# Urukul_FPGA_Config.net
KiCad netlist of a schematic drawn in Altium Designer
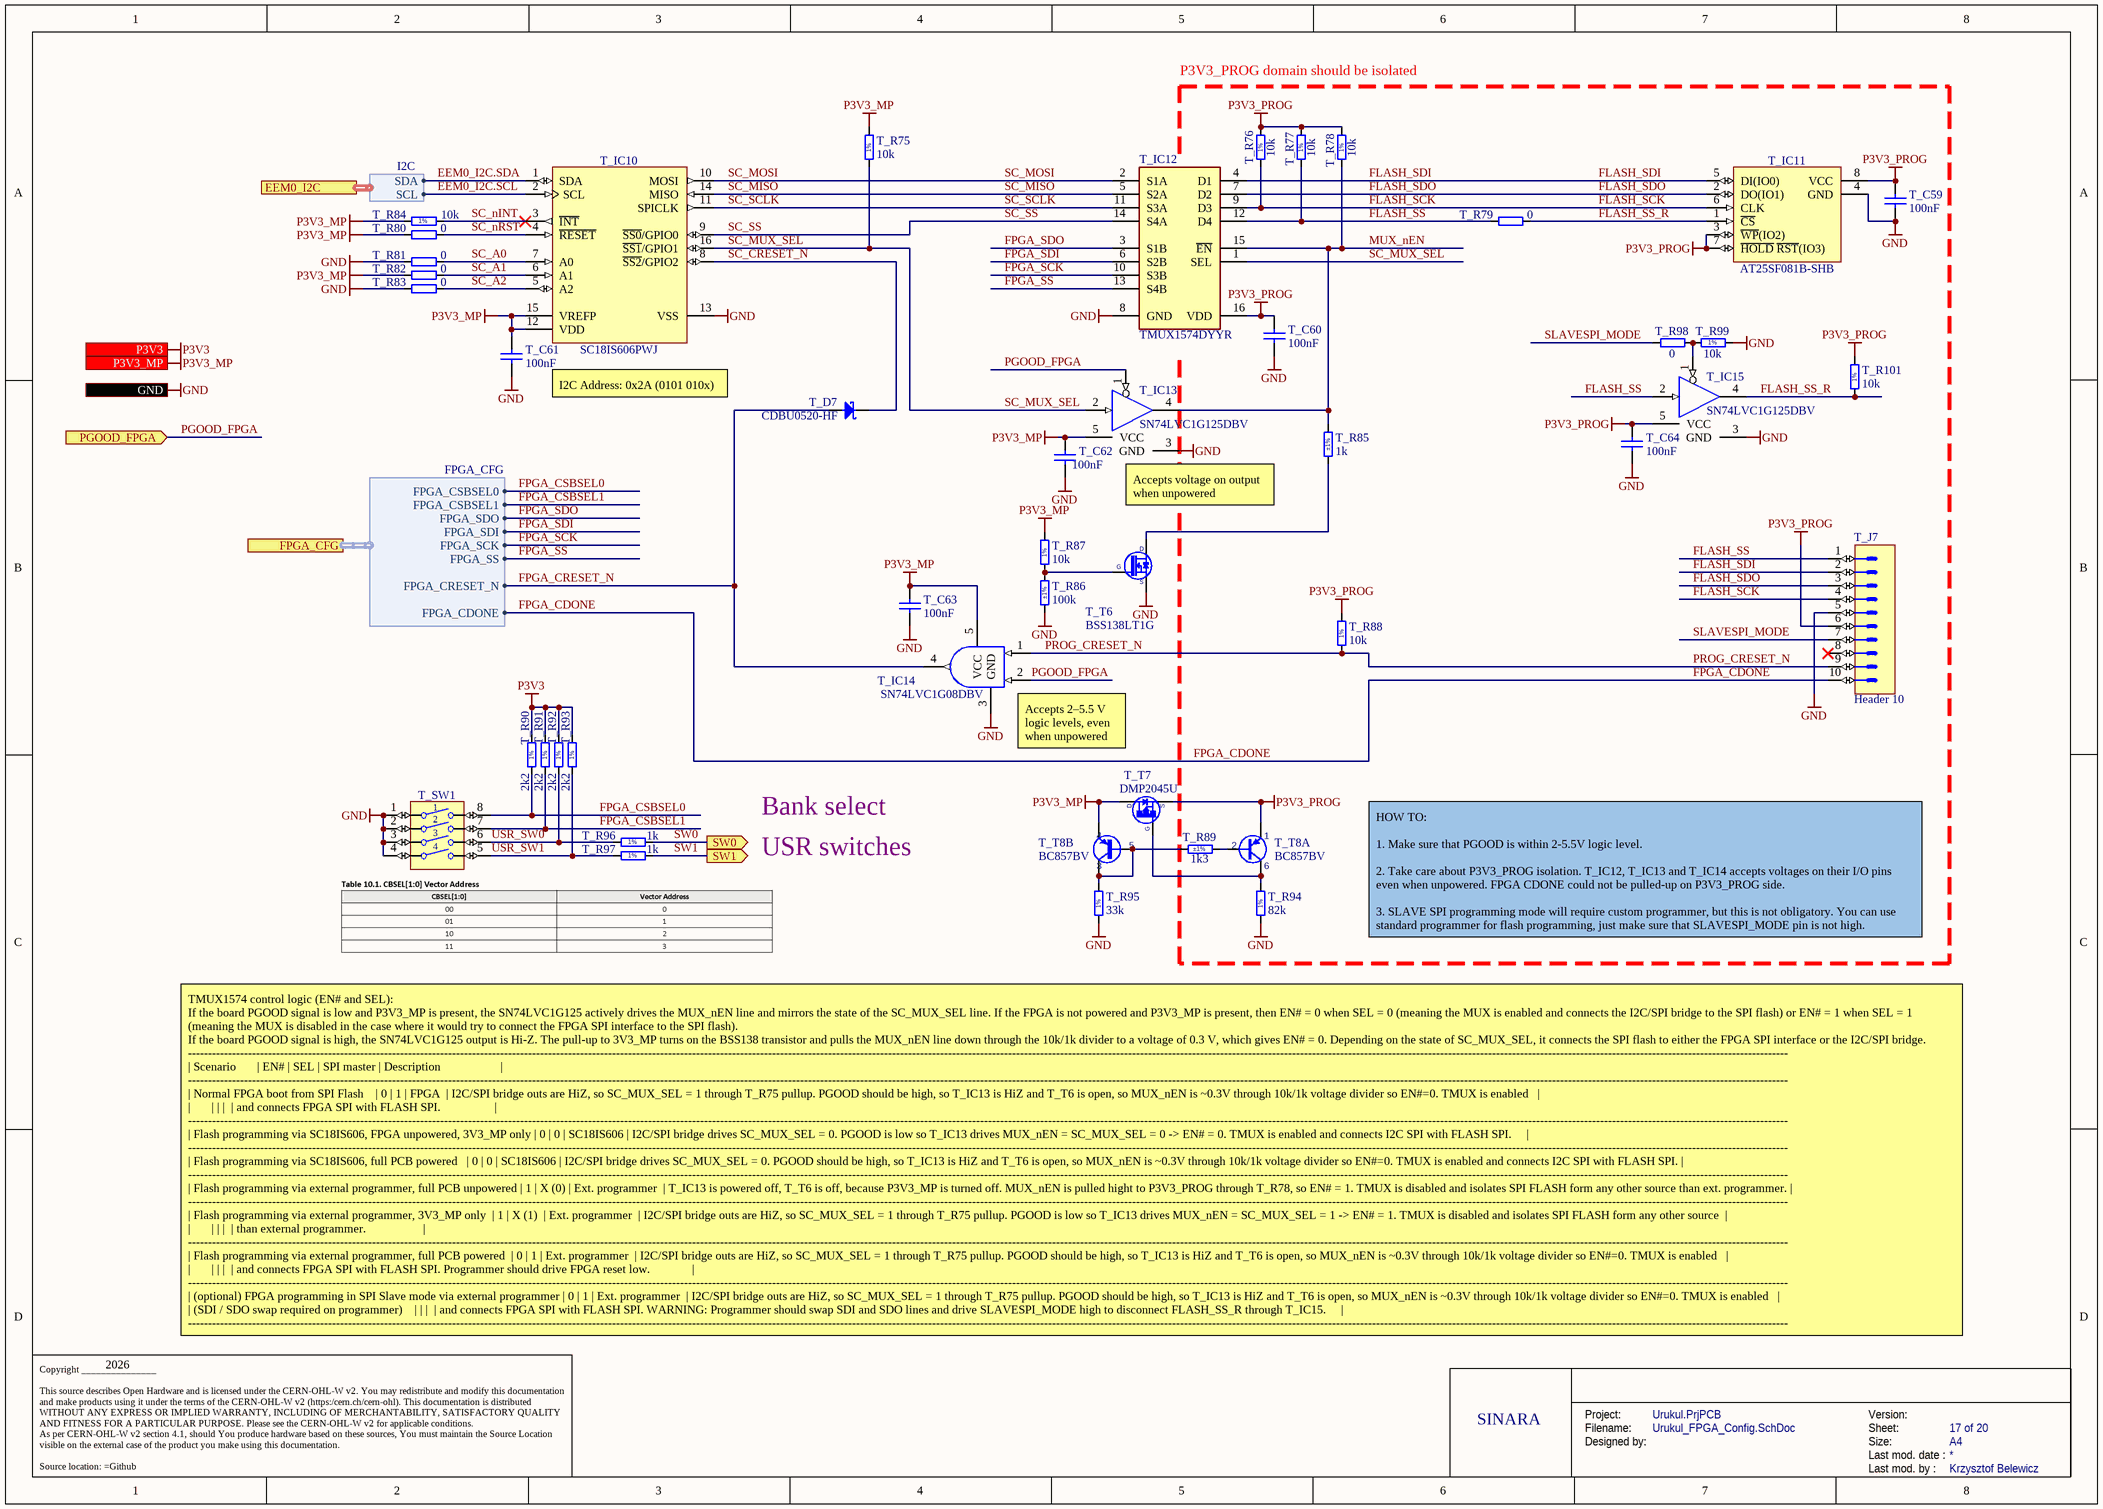
[diagram p0: Urukul_FPGA_Config.SchDoc]

(export (version "E")
  (design (tool "Eeschema 10.0.6"))
  (components
    (comp (ref "T_C59")
      (value "100nF")
      (footprint "CAPC1005X55N")
      (description "Non-polarised capacitor")
      (fields
        (field (name "PART NUMBER") "CC0402_100NF_16V_10%_X5R")
        (field (name "VOLTAGE") "16V")
        (field (name "AUTHOR") "CERN DEM JLC")
      )
      (libsource (lib "Capacitors") (part "Capacitor - non polarized"))
    )
    (comp (ref "T_C60")
      (value "100nF")
      (footprint "CAPC1005X55N")
      (description "Non-polarised capacitor")
      (fields
        (field (name "PART NUMBER") "CC0402_100NF_16V_10%_X5R")
        (field (name "VOLTAGE") "16V")
        (field (name "AUTHOR") "CERN DEM JLC")
      )
      (libsource (lib "Capacitors") (part "Capacitor - non polarized"))
    )
    (comp (ref "T_C61")
      (value "100nF")
      (footprint "CAPC1005X55N")
      (description "Non-polarised capacitor")
      (fields
        (field (name "PART NUMBER") "CC0402_100NF_16V_10%_X5R")
        (field (name "VOLTAGE") "16V")
        (field (name "AUTHOR") "CERN DEM JLC")
      )
      (libsource (lib "Capacitors") (part "Capacitor - non polarized"))
    )
    (comp (ref "T_C62")
      (value "100nF")
      (footprint "CAPC1005X55N")
      (description "Non-polarised capacitor")
      (fields
        (field (name "PART NUMBER") "CC0402_100NF_16V_10%_X5R")
        (field (name "VOLTAGE") "16V")
        (field (name "AUTHOR") "CERN DEM JLC")
      )
      (libsource (lib "Capacitors") (part "Capacitor - non polarized"))
    )
    (comp (ref "T_C63")
      (value "100nF")
      (footprint "CAPC1005X55N")
      (description "Non-polarised capacitor")
      (fields
        (field (name "PART NUMBER") "CC0402_100NF_16V_10%_X5R")
        (field (name "VOLTAGE") "16V")
        (field (name "AUTHOR") "CERN DEM JLC")
      )
      (libsource (lib "Capacitors") (part "Capacitor - non polarized"))
    )
    (comp (ref "T_C64")
      (value "100nF")
      (footprint "CAPC1005X55N")
      (description "Non-polarised capacitor")
      (fields
        (field (name "PART NUMBER") "CC0402_100NF_16V_10%_X5R")
        (field (name "VOLTAGE") "16V")
        (field (name "AUTHOR") "CERN DEM JLC")
      )
      (libsource (lib "Capacitors") (part "Capacitor - non polarized"))
    )
    (comp (ref "T_D7")
      (value "CDBU0520-HF")
      (footprint "SOD-523F")
      (description "Schottky Diode")
      (fields
        (field (name "VOLTAGE") "20V")
        (field (name "POWER") "500mA")
        (field (name "AUTHOR") "CERN DEM HF")
      )
      (libsource (lib "ICs And Semiconductors") (part "Diode Schottky"))
    )
    (comp (ref "T_IC10")
      (value "SC18IS606PWJ")
      (footprint "SOP65P640X110-16N")
      (description "I2C-bus to SPI bridge")
      (fields (field (name "MANUFACTURER") "NXP SEMICONDUCTORS") (field (name "AUTHOR") "GK"))
      (libsource (lib "ICS-logic") (part "SC18IS606PWJ"))
    )
    (comp (ref "T_IC11")
      (value "AT25SF081B-SHB")
      (footprint "SOIC127P790X216-8N")
      (description "8M-bit Serial Flash Memory with uniform 4KB sectors and Dual/Quad SPI and QPI")
      (fields (field (name "MANUFACTURER") "Renesas") (field (name "AUTHOR") "GK"))
      (libsource (lib "ICS-logic") (part "MEM_AT25SF081B-SHB"))
    )
    (comp (ref "T_IC12")
      (value "TMUX1574DYYR")
      (footprint "SamacSys:SOP50P326X110-16N")
      (description "Integrated Circuit")
      (fields (field (name "MOUSER PART NUMBER") "595-TMUX1574DYYR"))
      (libsource (lib "SamacSys") (part "TMUX1574DYYR"))
    )
    (comp (ref "T_IC13")
      (value "SN74LVC1G125DBV")
      (footprint "SOT95P280X145-5N")
      (description "Single Bus Buffer Gate With 3-State Output")
      (fields (field (name "MANUFACTURER") "TEXAS INSTRUMENTS") (field (name "AUTHOR") "CERN DEM HF"))
      (libsource (lib "ICs And Semiconductors") (part "741G125"))
    )
    (comp (ref "T_IC14")
      (value "SN74LVC1G08DBV")
      (footprint "SOT95P280X145-5N")
      (description "Single 2-Input AND Gate")
      (fields (field (name "MANUFACTURER") "TEXAS INSTRUMENTS") (field (name "AUTHOR") "CERN DEM JLC"))
      (libsource (lib "ICs And Semiconductors") (part "741G08"))
    )
    (comp (ref "T_IC15")
      (value "SN74LVC1G125DBV")
      (footprint "SOT95P280X145-5N")
      (description "Single Bus Buffer Gate With 3-State Output")
      (fields (field (name "MANUFACTURER") "TEXAS INSTRUMENTS") (field (name "AUTHOR") "CERN DEM HF"))
      (libsource (lib "ICs And Semiconductors") (part "741G125"))
    )
    (comp (ref "T_J7")
      (value "Header 10")
      (footprint "HARWIN_M20-9980546")
      (description "Connector 10 Male")
      (fields
        (field (name "PART NUMBER") "HARWIN_M20-9980546")
        (field (name "MANUFACTURER") "HARWIN")
        (field (name "AUTHOR") "CERN DEM MR")
      )
      (libsource (lib "Connectors") (part "Connector 10 Male"))
    )
    (comp (ref "T_R75")
      (value "10k")
      (footprint "RESC1005X40N")
      (description "Resistor - 1%")
      (fields
        (field (name "PART NUMBER") "R0402_10K_1%_0.0625W_100PPM")
        (field (name "POWER") "0.0625W")
        (field (name "AUTHOR") "CERN DEM JLC")
      )
      (libsource (lib "Resistors") (part "Resistor - 1%"))
    )
    (comp (ref "T_R76")
      (value "10k")
      (footprint "RESC1005X40N")
      (description "Resistor - 1%")
      (fields
        (field (name "PART NUMBER") "R0402_10K_1%_0.0625W_100PPM")
        (field (name "POWER") "0.0625W")
        (field (name "AUTHOR") "CERN DEM JLC")
      )
      (libsource (lib "Resistors") (part "Resistor - 1%"))
    )
    (comp (ref "T_R77")
      (value "10k")
      (footprint "RESC1005X40N")
      (description "Resistor - 1%")
      (fields
        (field (name "PART NUMBER") "R0402_10K_1%_0.0625W_100PPM")
        (field (name "POWER") "0.0625W")
        (field (name "AUTHOR") "CERN DEM JLC")
      )
      (libsource (lib "Resistors") (part "Resistor - 1%"))
    )
    (comp (ref "T_R78")
      (value "10k")
      (footprint "RESC1005X40N")
      (description "Resistor - 1%")
      (fields
        (field (name "PART NUMBER") "R0402_10K_1%_0.0625W_100PPM")
        (field (name "POWER") "0.0625W")
        (field (name "AUTHOR") "CERN DEM JLC")
      )
      (libsource (lib "Resistors") (part "Resistor - 1%"))
    )
    (comp (ref "T_R79")
      (value "0")
      (footprint "RESC1005X40N")
      (description "Resistor")
      (fields
        (field (name "PART NUMBER") "R0402_0R_JUMPER")
        (field (name "MANUFACTURER") "GENERIC")
        (field (name "AUTHOR") "CERN DEM JLC")
      )
      (libsource (lib "Resistors") (part "Resistor"))
    )
    (comp (ref "T_R80")
      (value "0")
      (footprint "RESC1005X40N")
      (description "Resistor")
      (fields
        (field (name "PART NUMBER") "R0402_0R_JUMPER")
        (field (name "MANUFACTURER") "GENERIC")
        (field (name "AUTHOR") "CERN DEM JLC")
      )
      (libsource (lib "Resistors") (part "Resistor"))
    )
    (comp (ref "T_R81")
      (value "0")
      (footprint "RESC1005X40N")
      (description "Resistor")
      (fields
        (field (name "PART NUMBER") "R0402_0R_JUMPER")
        (field (name "MANUFACTURER") "GENERIC")
        (field (name "AUTHOR") "CERN DEM JLC")
      )
      (libsource (lib "Resistors") (part "Resistor"))
    )
    (comp (ref "T_R82")
      (value "0")
      (footprint "RESC1005X40N")
      (description "Resistor")
      (fields
        (field (name "PART NUMBER") "R0402_0R_JUMPER")
        (field (name "MANUFACTURER") "GENERIC")
        (field (name "AUTHOR") "CERN DEM JLC")
      )
      (libsource (lib "Resistors") (part "Resistor"))
    )
    (comp (ref "T_R83")
      (value "0")
      (footprint "RESC1005X40N")
      (description "Resistor")
      (fields
        (field (name "PART NUMBER") "R0402_0R_JUMPER")
        (field (name "MANUFACTURER") "GENERIC")
        (field (name "AUTHOR") "CERN DEM JLC")
      )
      (libsource (lib "Resistors") (part "Resistor"))
    )
    (comp (ref "T_R84")
      (value "10k")
      (footprint "RESC1005X40N")
      (description "Resistor - 1%")
      (fields
        (field (name "PART NUMBER") "R0402_10K_1%_0.0625W_100PPM")
        (field (name "POWER") "0.0625W")
        (field (name "AUTHOR") "CERN DEM JLC")
      )
      (libsource (lib "Resistors") (part "Resistor - 1%"))
    )
    (comp (ref "T_R85")
      (value "1k")
      (footprint "RESC1005X40N")
      (description "Resistor - 1%")
      (fields
        (field (name "TOLERANCE") "±1%")
        (field (name "PART NUMBER") "R0402_1K_1%_0.0625W_100PPM")
        (field (name "POWER") "0.0625W")
        (field (name "AUTHOR") "CERN DEM JLC")
      )
      (libsource (lib "Resistors") (part "Resistor - 1%"))
    )
    (comp (ref "T_R86")
      (value "100k")
      (footprint "RESC1005X40N")
      (description "Resistor - 1%")
      (fields
        (field (name "TOLERANCE") "±1%")
        (field (name "PART NUMBER") "R0402_100K_1%_0.0625W_100PPM")
        (field (name "POWER") "0.0625W")
        (field (name "AUTHOR") "CERN DEM JLC")
      )
      (libsource (lib "Resistors") (part "Resistor - 1%"))
    )
    (comp (ref "T_R87")
      (value "10k")
      (footprint "RESC1005X40N")
      (description "Resistor - 1%")
      (fields
        (field (name "PART NUMBER") "R0402_10K_1%_0.0625W_100PPM")
        (field (name "POWER") "0.0625W")
        (field (name "AUTHOR") "CERN DEM JLC")
      )
      (libsource (lib "Resistors") (part "Resistor - 1%"))
    )
    (comp (ref "T_R88")
      (value "10k")
      (footprint "RESC1005X40N")
      (description "Resistor - 1%")
      (fields
        (field (name "PART NUMBER") "R0402_10K_1%_0.0625W_100PPM")
        (field (name "POWER") "0.0625W")
        (field (name "AUTHOR") "CERN DEM JLC")
      )
      (libsource (lib "Resistors") (part "Resistor - 1%"))
    )
    (comp (ref "T_R89")
      (value "1k3")
      (footprint "RESC1005X40N")
      (description "Resistor - 1%")
      (fields
        (field (name "TOLERANCE") "±1%")
        (field (name "PART NUMBER") "R0402_1K3_1%_0.0625W_100PPM")
        (field (name "POWER") "0.0625W")
        (field (name "AUTHOR") "CERN DEM JLC")
      )
      (libsource (lib "Resistors") (part "Resistor - 1%"))
    )
    (comp (ref "T_R90")
      (value "2k2")
      (footprint "RESC1005X40N")
      (description "Resistor - 1%")
      (fields
        (field (name "PART NUMBER") "R0402_2K2_1%_0.0625W_100PPM")
        (field (name "POWER") "0.0625W")
        (field (name "AUTHOR") "CERN DEM JLC")
      )
      (libsource (lib "Resistors") (part "Resistor - 1%"))
    )
    (comp (ref "T_R91")
      (value "2k2")
      (footprint "RESC1005X40N")
      (description "Resistor - 1%")
      (fields
        (field (name "PART NUMBER") "R0402_2K2_1%_0.0625W_100PPM")
        (field (name "POWER") "0.0625W")
        (field (name "AUTHOR") "CERN DEM JLC")
      )
      (libsource (lib "Resistors") (part "Resistor - 1%"))
    )
    (comp (ref "T_R92")
      (value "2k2")
      (footprint "RESC1005X40N")
      (description "Resistor - 1%")
      (fields
        (field (name "PART NUMBER") "R0402_2K2_1%_0.0625W_100PPM")
        (field (name "POWER") "0.0625W")
        (field (name "AUTHOR") "CERN DEM JLC")
      )
      (libsource (lib "Resistors") (part "Resistor - 1%"))
    )
    (comp (ref "T_R93")
      (value "2k2")
      (footprint "RESC1005X40N")
      (description "Resistor - 1%")
      (fields
        (field (name "PART NUMBER") "R0402_2K2_1%_0.0625W_100PPM")
        (field (name "POWER") "0.0625W")
        (field (name "AUTHOR") "CERN DEM JLC")
      )
      (libsource (lib "Resistors") (part "Resistor - 1%"))
    )
    (comp (ref "T_R94")
      (value "82k")
      (footprint "RESC1608X55N")
      (description "Resistor - 1%")
      (fields
        (field (name "PART NUMBER") "R0603_82K_1%_0.1W_100PPM")
        (field (name "POWER") "0.1W")
        (field (name "AUTHOR") "CERN DEM JLC")
      )
      (libsource (lib "Resistors") (part "Resistor - 1%"))
    )
    (comp (ref "T_R95")
      (value "33k")
      (footprint "RESC1005X40N")
      (description "Resistor - 1%")
      (fields
        (field (name "PART NUMBER") "R0402_33K_1%_0.0625W_100PPM")
        (field (name "POWER") "0.0625W")
        (field (name "AUTHOR") "CERN DEM JLC")
      )
      (libsource (lib "Resistors") (part "Resistor - 1%"))
    )
    (comp (ref "T_R96")
      (value "1k")
      (footprint "RESC1005X40N")
      (description "Resistor - 1%")
      (fields
        (field (name "PART NUMBER") "R0402_1K_1%_0.0625W_100PPM")
        (field (name "POWER") "0.0625W")
        (field (name "AUTHOR") "CERN DEM JLC")
      )
      (libsource (lib "Resistors") (part "Resistor - 1%"))
    )
    (comp (ref "T_R97")
      (value "1k")
      (footprint "RESC1005X40N")
      (description "Resistor - 1%")
      (fields
        (field (name "PART NUMBER") "R0402_1K_1%_0.0625W_100PPM")
        (field (name "POWER") "0.0625W")
        (field (name "AUTHOR") "CERN DEM JLC")
      )
      (libsource (lib "Resistors") (part "Resistor - 1%"))
    )
    (comp (ref "T_R98")
      (value "0")
      (footprint "RESC1005X40N")
      (description "Resistor")
      (fields
        (field (name "PART NUMBER") "R0402_0R_JUMPER")
        (field (name "MANUFACTURER") "GENERIC")
        (field (name "AUTHOR") "CERN DEM JLC")
      )
      (libsource (lib "Resistors") (part "Resistor"))
    )
    (comp (ref "T_R99")
      (value "10k")
      (footprint "RESC1005X40N")
      (description "Resistor - 1%")
      (fields
        (field (name "PART NUMBER") "R0402_10K_1%_0.0625W_100PPM")
        (field (name "POWER") "0.0625W")
        (field (name "AUTHOR") "CERN DEM JLC")
      )
      (libsource (lib "Resistors") (part "Resistor - 1%"))
    )
    (comp (ref "T_R101")
      (value "10k")
      (footprint "RESC1005X40N")
      (description "Resistor - 1%")
      (fields
        (field (name "PART NUMBER") "R0402_10K_1%_0.0625W_100PPM")
        (field (name "POWER") "0.0625W")
        (field (name "AUTHOR") "CERN DEM JLC")
      )
      (libsource (lib "Resistors") (part "Resistor - 1%"))
    )
    (comp (ref "T_SW1")
      (value "Switch")
      (footprint "SW_TYCO_1571983-4")
      (description "4 Ways SPST DIP Switch")
      (fields
        (field (name "PART NUMBER") "SW_TYCO_1571983-4")
        (field (name "MANUFACTURER") "TYCO")
        (field (name "AUTHOR") "CERN DEM JLC")
      )
      (libsource (lib "Eletro-mechanical") (part "SW 4x SPST DIP Switch"))
    )
    (comp (ref "T_T6")
      (value "BSS138LT1G")
      (footprint "SOT95P240X110-3N")
      (description "N-CHANNEL MOSFET WITH DIODE")
      (fields
        (field (name "MANUFACTURER") "ON SEMICONDUCTOR")
        (field (name "MANUFACTURER PART NUMBER") "BSS138L")
        (field (name "AUTHOR") "CERN DEM JLC")
      )
      (libsource (lib "ICs And Semiconductors") (part "N-MOSFET-D 1G 2S 3D"))
    )
    (comp (ref "T_T7")
      (value "DMP2045U")
      (footprint "SOT95P240X110-3N")
      (description "P-CHANNEL MOSFET WITH DIODE")
      (fields (field (name "MANUFACTURER") "DIODES INCORPORATED") (field (name "AUTHOR") "CERN DEM HF"))
      (libsource (lib "ICs And Semiconductors") (part "P-MOSFET-D 1G 2S 3D"))
    )
    (comp (ref "T_T8")
      (value "BC857BV")
      (footprint "SOTFL50P160X60-6N")
      (description "45V, 100mA PNP General Purpose Double Transistor")
      (fields (field (name "MANUFACTURER") "NXP SEMICONDUCTORS") (field (name "AUTHOR") "CERN DEM JLC"))
      (libsource (lib "") (part "BC857BV_1"))
    )
  )
  (nets
    (net (code "3") (name "/EEM0_I2C.SCL") (class "Default")
      (node (ref "T_IC10") (pin "2") (pinfunction "SCL_2") (pintype "input"))
    )
    (net (code "4") (name "/EEM0_I2C.SDA") (class "Default")
      (node (ref "T_IC10") (pin "1") (pinfunction "SDA_1") (pintype "bidirectional"))
    )
    (net (code "5") (name "/FLASH_SCK") (class "Default")
      (node (ref "T_IC11") (pin "6") (pinfunction "CLK_6") (pintype "input"))
      (node (ref "T_IC12") (pin "9") (pinfunction "D3_9") (pintype "passive"))
      (node (ref "T_J7") (pin "4") (pinfunction "4_4") (pintype "bidirectional"))
      (node (ref "T_R76") (pin "1") (pinfunction "1_1") (pintype "passive"))
    )
    (net (code "6") (name "/FLASH_SDI") (class "Default")
      (node (ref "T_IC11") (pin "5") (pinfunction "DI(IO0)_5") (pintype "bidirectional"))
      (node (ref "T_IC12") (pin "4") (pinfunction "D1_4") (pintype "passive"))
      (node (ref "T_J7") (pin "2") (pinfunction "2_2") (pintype "bidirectional"))
    )
    (net (code "7") (name "/FLASH_SDO") (class "Default")
      (node (ref "T_IC11") (pin "2") (pinfunction "DO(IO1)_2") (pintype "bidirectional"))
      (node (ref "T_IC12") (pin "7") (pinfunction "D2_7") (pintype "passive"))
      (node (ref "T_J7") (pin "3") (pinfunction "3_3") (pintype "bidirectional"))
    )
    (net (code "8") (name "/FLASH_SS") (class "Default")
      (node (ref "T_IC12") (pin "12") (pinfunction "D4_12") (pintype "passive"))
      (node (ref "T_IC15") (pin "2") (pinfunction "IN_2") (pintype "input"))
      (node (ref "T_J7") (pin "1") (pinfunction "1_1") (pintype "bidirectional"))
      (node (ref "T_R77") (pin "1") (pinfunction "1_1") (pintype "passive"))
      (node (ref "T_R79") (pin "1") (pinfunction "1_1") (pintype "passive"))
    )
    (net (code "9") (name "/FLASH_SS_R") (class "Default")
      (node (ref "T_IC11") (pin "1") (pinfunction "~{CS}_1") (pintype "input"))
      (node (ref "T_IC15") (pin "4") (pinfunction "OUT_4") (pintype "tri_state"))
      (node (ref "T_R101") (pin "1") (pinfunction "1_1") (pintype "passive"))
      (node (ref "T_R79") (pin "2") (pinfunction "2_2") (pintype "passive"))
    )
    (net (code "10") (name "/FPGA_CDONE") (class "Default")
      (node (ref "T_J7") (pin "10") (pinfunction "10_10") (pintype "bidirectional"))
    )
    (net (code "11") (name "/FPGA_CRESET_N") (class "Default")
      (node (ref "T_D7") (pin "2") (pinfunction "A_2") (pintype "passive"))
      (node (ref "T_IC14") (pin "4") (pinfunction "Y_4") (pintype "output"))
    )
    (net (code "12") (name "/FPGA_CSBSEL0") (class "Default")
      (node (ref "T_R90") (pin "1") (pinfunction "1_1") (pintype "passive"))
      (node (ref "T_SW1") (pin "8") (pinfunction "8_8") (pintype "bidirectional"))
    )
    (net (code "13") (name "/FPGA_CSBSEL1") (class "Default")
      (node (ref "T_R91") (pin "1") (pinfunction "1_1") (pintype "passive"))
      (node (ref "T_SW1") (pin "7") (pinfunction "7_7") (pintype "bidirectional"))
    )
    (net (code "14") (name "/FPGA_SCK") (class "Default")
      (node (ref "T_IC12") (pin "10") (pinfunction "S3B_10") (pintype "passive"))
    )
    (net (code "15") (name "/FPGA_SDI") (class "Default")
      (node (ref "T_IC12") (pin "6") (pinfunction "S2B_6") (pintype "passive"))
    )
    (net (code "16") (name "/FPGA_SDO") (class "Default")
      (node (ref "T_IC12") (pin "3") (pinfunction "S1B_3") (pintype "passive"))
    )
    (net (code "17") (name "/FPGA_SS") (class "Default")
      (node (ref "T_IC12") (pin "13") (pinfunction "S4B_13") (pintype "passive"))
    )
    (net (code "18") (name "/MUX_nEN") (class "Default")
      (node (ref "T_IC12") (pin "15") (pinfunction "~{EN}_15") (pintype "passive"))
      (node (ref "T_IC13") (pin "4") (pinfunction "OUT_4") (pintype "tri_state"))
      (node (ref "T_R78") (pin "1") (pinfunction "1_1") (pintype "passive"))
      (node (ref "T_R85") (pin "2") (pinfunction "2_2") (pintype "passive"))
    )
    (net (code "19") (name "/PGOOD_FPGA") (class "Default")
      (node (ref "T_IC13") (pin "1") (pinfunction "~{G}_1") (pintype "input"))
      (node (ref "T_IC14") (pin "2") (pinfunction "B_2") (pintype "input"))
    )
    (net (code "20") (name "/PROG_CRESET_N") (class "Default")
      (node (ref "T_IC14") (pin "1") (pinfunction "A_1") (pintype "input"))
      (node (ref "T_J7") (pin "9") (pinfunction "9_9") (pintype "bidirectional"))
      (node (ref "T_R88") (pin "1") (pinfunction "1_1") (pintype "passive"))
    )
    (net (code "21") (name "/SC_A0") (class "Default")
      (node (ref "T_IC10") (pin "7") (pinfunction "A0_7") (pintype "input"))
      (node (ref "T_R81") (pin "1") (pinfunction "1_1") (pintype "passive"))
    )
    (net (code "22") (name "/SC_A1") (class "Default")
      (node (ref "T_IC10") (pin "6") (pinfunction "A1_6") (pintype "input"))
      (node (ref "T_R82") (pin "1") (pinfunction "1_1") (pintype "passive"))
    )
    (net (code "23") (name "/SC_A2") (class "Default")
      (node (ref "T_IC10") (pin "5") (pinfunction "A2_5") (pintype "bidirectional"))
      (node (ref "T_R83") (pin "1") (pinfunction "1_1") (pintype "passive"))
    )
    (net (code "24") (name "/SC_CRESET_N") (class "Default")
      (node (ref "T_D7") (pin "1") (pinfunction "C_1") (pintype "passive"))
      (node (ref "T_IC10") (pin "8") (pinfunction "~{SS2}/GPIO2_8") (pintype "bidirectional"))
    )
    (net (code "25") (name "/SC_MISO") (class "Default")
      (node (ref "T_IC10") (pin "14") (pinfunction "MISO_14") (pintype "input"))
      (node (ref "T_IC12") (pin "5") (pinfunction "S2A_5") (pintype "passive"))
    )
    (net (code "26") (name "/SC_MOSI") (class "Default")
      (node (ref "T_IC10") (pin "10") (pinfunction "MOSI_10") (pintype "output"))
      (node (ref "T_IC12") (pin "2") (pinfunction "S1A_2") (pintype "passive"))
    )
    (net (code "27") (name "/SC_MUX_SEL") (class "Default")
      (node (ref "T_IC10") (pin "16") (pinfunction "~{SS1}/GPIO1_16") (pintype "bidirectional"))
      (node (ref "T_IC12") (pin "1") (pinfunction "SEL_1") (pintype "passive"))
      (node (ref "T_IC13") (pin "2") (pinfunction "IN_2") (pintype "input"))
      (node (ref "T_R75") (pin "1") (pinfunction "1_1") (pintype "passive"))
    )
    (net (code "28") (name "/SC_SCLK") (class "Default")
      (node (ref "T_IC10") (pin "11") (pinfunction "SPICLK_11") (pintype "output"))
      (node (ref "T_IC12") (pin "11") (pinfunction "S3A_11") (pintype "passive"))
    )
    (net (code "29") (name "/SC_SS") (class "Default")
      (node (ref "T_IC10") (pin "9") (pinfunction "~{SS0}/GPIO0_9") (pintype "bidirectional"))
      (node (ref "T_IC12") (pin "14") (pinfunction "S4A_14") (pintype "passive"))
    )
    (net (code "30") (name "/SC_nINT") (class "Default")
      (node (ref "T_IC10") (pin "3") (pinfunction "~{INT}_3") (pintype "output"))
      (node (ref "T_R84") (pin "2") (pinfunction "2_2") (pintype "passive"))
    )
    (net (code "31") (name "/SC_nRST") (class "Default")
      (node (ref "T_IC10") (pin "4") (pinfunction "~{RESET}_4") (pintype "input"))
      (node (ref "T_R80") (pin "1") (pinfunction "1_1") (pintype "passive"))
    )
    (net (code "32") (name "/SLAVESPI_MODE") (class "Default")
      (node (ref "T_J7") (pin "7") (pinfunction "7_7") (pintype "bidirectional"))
      (node (ref "T_R98") (pin "1") (pinfunction "1_1") (pintype "passive"))
    )
    (net (code "33") (name "/SW0") (class "Default")
      (node (ref "T_R96") (pin "1") (pinfunction "1_1") (pintype "passive"))
    )
    (net (code "34") (name "/SW1") (class "Default")
      (node (ref "T_R97") (pin "1") (pinfunction "1_1") (pintype "passive"))
    )
    (net (code "35") (name "/USR_SW0") (class "Default")
      (node (ref "T_R92") (pin "1") (pinfunction "1_1") (pintype "passive"))
      (node (ref "T_R96") (pin "2") (pinfunction "2_2") (pintype "passive"))
      (node (ref "T_SW1") (pin "6") (pinfunction "6_6") (pintype "bidirectional"))
    )
    (net (code "36") (name "/USR_SW1") (class "Default")
      (node (ref "T_R93") (pin "1") (pinfunction "1_1") (pintype "passive"))
      (node (ref "T_R97") (pin "2") (pinfunction "2_2") (pintype "passive"))
      (node (ref "T_SW1") (pin "5") (pinfunction "5_5") (pintype "bidirectional"))
    )
    (net (code "39") (name "GND") (class "Default")
      (node (ref "T_C59") (pin "1") (pinfunction "1_1") (pintype "passive"))
      (node (ref "T_C60") (pin "1") (pinfunction "1_1") (pintype "passive"))
      (node (ref "T_C61") (pin "1") (pinfunction "1_1") (pintype "passive"))
      (node (ref "T_C62") (pin "1") (pinfunction "1_1") (pintype "passive"))
      (node (ref "T_C63") (pin "1") (pinfunction "1_1") (pintype "passive"))
      (node (ref "T_C64") (pin "1") (pinfunction "1_1") (pintype "passive"))
      (node (ref "T_IC10") (pin "13") (pinfunction "VSS_13") (pintype "power_in"))
      (node (ref "T_IC11") (pin "4") (pinfunction "GND_4") (pintype "power_in"))
      (node (ref "T_IC12") (pin "8") (pinfunction "GND_8") (pintype "passive"))
      (node (ref "T_IC13") (pin "3") (pinfunction "GND_3") (pintype "power_in"))
      (node (ref "T_IC14") (pin "3") (pinfunction "GND_3") (pintype "power_in"))
      (node (ref "T_IC15") (pin "3") (pinfunction "GND_3") (pintype "power_in"))
      (node (ref "T_J7") (pin "5") (pinfunction "5_5") (pintype "bidirectional"))
      (node (ref "T_R81") (pin "2") (pinfunction "2_2") (pintype "passive"))
      (node (ref "T_R83") (pin "2") (pinfunction "2_2") (pintype "passive"))
      (node (ref "T_R86") (pin "2") (pinfunction "2_2") (pintype "passive"))
      (node (ref "T_R94") (pin "1") (pinfunction "1_1") (pintype "passive"))
      (node (ref "T_R95") (pin "1") (pinfunction "1_1") (pintype "passive"))
      (node (ref "T_R99") (pin "2") (pinfunction "2_2") (pintype "passive"))
      (node (ref "T_SW1") (pin "1") (pinfunction "1_1") (pintype "bidirectional"))
      (node (ref "T_SW1") (pin "2") (pinfunction "2_2") (pintype "bidirectional"))
      (node (ref "T_SW1") (pin "3") (pinfunction "3_3") (pintype "bidirectional"))
      (node (ref "T_SW1") (pin "4") (pinfunction "4_4") (pintype "bidirectional"))
      (node (ref "T_T6") (pin "2") (pinfunction "S_2") (pintype "passive"))
    )
    (net (code "40") (name "Net-(T_IC15-~{G})") (class "Default")
      (node (ref "T_IC15") (pin "1") (pinfunction "~{G}_1") (pintype "input"))
      (node (ref "T_R98") (pin "2") (pinfunction "2_2") (pintype "passive"))
      (node (ref "T_R99") (pin "1") (pinfunction "1_1") (pintype "passive"))
    )
    (net (code "41") (name "Net-(T_T6-D)") (class "Default")
      (node (ref "T_R85") (pin "1") (pinfunction "1_1") (pintype "passive"))
      (node (ref "T_T6") (pin "3") (pinfunction "D_3") (pintype "passive"))
    )
    (net (code "42") (name "Net-(T_T6-G)") (class "Default")
      (node (ref "T_R86") (pin "1") (pinfunction "1_1") (pintype "passive"))
      (node (ref "T_R87") (pin "1") (pinfunction "1_1") (pintype "passive"))
      (node (ref "T_T6") (pin "1") (pinfunction "G_1") (pintype "passive"))
    )
    (net (code "43") (name "Net-(T_T7-G)") (class "Default")
      (node (ref "T_R94") (pin "2") (pinfunction "2_2") (pintype "passive"))
      (node (ref "T_T7") (pin "1") (pinfunction "G_1") (pintype "passive"))
      (node (ref "T_T8") (pin "6") (pinfunction "C_6") (pintype "passive"))
    )
    (net (code "44") (name "Net-(T_T8A-B)") (class "Default")
      (node (ref "T_R89") (pin "1") (pinfunction "1_1") (pintype "passive"))
      (node (ref "T_T8") (pin "2") (pinfunction "B_2") (pintype "passive"))
    )
    (net (code "45") (name "Net-(T_T8B-B)") (class "Default")
      (node (ref "T_R89") (pin "2") (pinfunction "2_2") (pintype "passive"))
      (node (ref "T_R95") (pin "2") (pinfunction "2_2") (pintype "passive"))
      (node (ref "T_T8") (pin "3") (pinfunction "C_3") (pintype "passive"))
      (node (ref "T_T8") (pin "5") (pinfunction "B_5") (pintype "passive"))
    )
    (net (code "46") (name "P3V3") (class "Default")
      (node (ref "T_R90") (pin "2") (pinfunction "2_2") (pintype "passive"))
      (node (ref "T_R91") (pin "2") (pinfunction "2_2") (pintype "passive"))
      (node (ref "T_R92") (pin "2") (pinfunction "2_2") (pintype "passive"))
      (node (ref "T_R93") (pin "2") (pinfunction "2_2") (pintype "passive"))
    )
    (net (code "47") (name "P3V3_MP") (class "Default")
      (node (ref "T_C61") (pin "2") (pinfunction "2_2") (pintype "passive"))
      (node (ref "T_C62") (pin "2") (pinfunction "2_2") (pintype "passive"))
      (node (ref "T_C63") (pin "2") (pinfunction "2_2") (pintype "passive"))
      (node (ref "T_IC10") (pin "12") (pinfunction "VDD_12") (pintype "power_in"))
      (node (ref "T_IC10") (pin "15") (pinfunction "VREFP_15") (pintype "power_in"))
      (node (ref "T_IC13") (pin "5") (pinfunction "VCC_5") (pintype "power_in"))
      (node (ref "T_IC14") (pin "5") (pinfunction "VCC_5") (pintype "power_in"))
      (node (ref "T_R75") (pin "2") (pinfunction "2_2") (pintype "passive"))
      (node (ref "T_R80") (pin "2") (pinfunction "2_2") (pintype "passive"))
      (node (ref "T_R82") (pin "2") (pinfunction "2_2") (pintype "passive"))
      (node (ref "T_R84") (pin "1") (pinfunction "1_1") (pintype "passive"))
      (node (ref "T_R87") (pin "2") (pinfunction "2_2") (pintype "passive"))
      (node (ref "T_T7") (pin "3") (pinfunction "D_3") (pintype "passive"))
      (node (ref "T_T8") (pin "4") (pinfunction "E_4") (pintype "passive"))
    )
    (net (code "48") (name "P3V3_PROG") (class "Default")
      (node (ref "T_C59") (pin "2") (pinfunction "2_2") (pintype "passive"))
      (node (ref "T_C60") (pin "2") (pinfunction "2_2") (pintype "passive"))
      (node (ref "T_C64") (pin "2") (pinfunction "2_2") (pintype "passive"))
      (node (ref "T_IC11") (pin "3") (pinfunction "~{WP}(IO2)_3") (pintype "bidirectional"))
      (node (ref "T_IC11") (pin "7") (pinfunction "~{HOLD}_~{RST}(IO3)_7") (pintype "bidirectional"))
      (node (ref "T_IC11") (pin "8") (pinfunction "VCC_8") (pintype "power_in"))
      (node (ref "T_IC12") (pin "16") (pinfunction "VDD_16") (pintype "passive"))
      (node (ref "T_IC15") (pin "5") (pinfunction "VCC_5") (pintype "power_in"))
      (node (ref "T_J7") (pin "6") (pinfunction "6_6") (pintype "bidirectional"))
      (node (ref "T_R101") (pin "2") (pinfunction "2_2") (pintype "passive"))
      (node (ref "T_R76") (pin "2") (pinfunction "2_2") (pintype "passive"))
      (node (ref "T_R77") (pin "2") (pinfunction "2_2") (pintype "passive"))
      (node (ref "T_R78") (pin "2") (pinfunction "2_2") (pintype "passive"))
      (node (ref "T_R88") (pin "2") (pinfunction "2_2") (pintype "passive"))
      (node (ref "T_T7") (pin "2") (pinfunction "S_2") (pintype "passive"))
      (node (ref "T_T8") (pin "1") (pinfunction "E_1") (pintype "passive"))
    )
    (net (code "49") (name "unconnected-(T_J7-Pad8)") (class "Default")
      (node (ref "T_J7") (pin "8") (pinfunction "8_8") (pintype "bidirectional+no_connect"))
    )
  )
)
